# i2c_io_expander.net
KiCad netlist of a schematic drawn in EAGLE
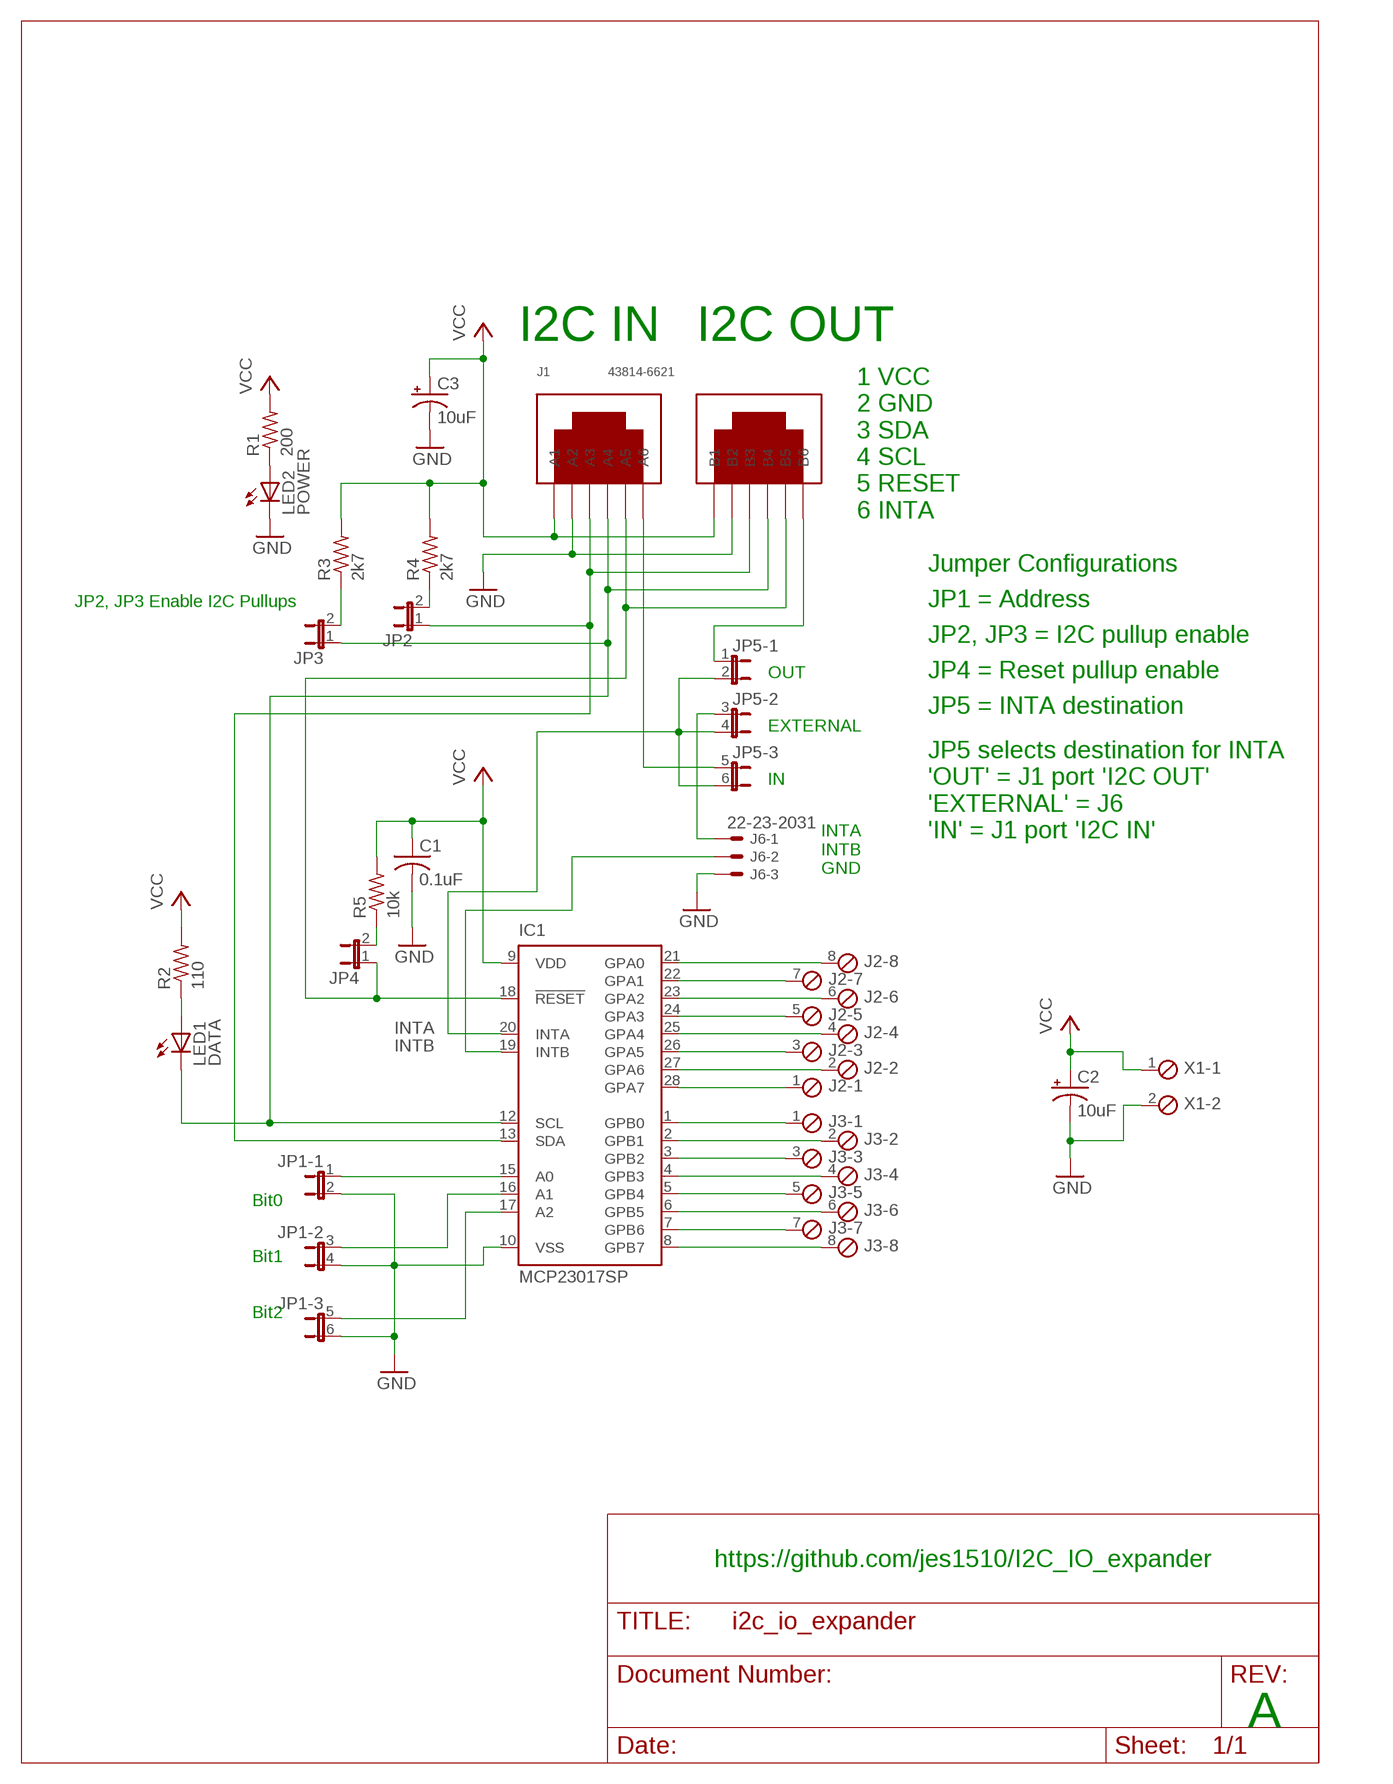
[diagram p0: schematic, sheet 1]

(export (version "E")
  (design (tool "Eeschema 10.0.6"))
  (components
    (comp (ref "C1")
      (value "0.1uF")
      (footprint "eagle-import:C025-025X050")
      (libsource (lib "eagle-import") (part "C-US025-025X050"))
    )
    (comp (ref "C2")
      (value "10uF")
      (footprint "eagle-import:E5-6")
      (libsource (lib "eagle-import") (part "CPOL-USE5-6"))
    )
    (comp (ref "C3")
      (value "10uF")
      (footprint "eagle-import:E5-6")
      (libsource (lib "eagle-import") (part "CPOL-USE5-6"))
    )
    (comp (ref "IC1")
      (value "MCP23017SP")
      (footprint "eagle-import:DIL28-3")
      (libsource (lib "eagle-import") (part "MCP23017SP"))
    )
    (comp (ref "J1")
      (value "43814-6621")
      (footprint "eagle-import:43814-6621")
      (fields (field (name "MF") "MOLEX"))
      (libsource (lib "eagle-import") (part "43814-6621"))
    )
    (comp (ref "J2")
      (value "MPT8")
      (footprint "eagle-import:8POL254")
      (fields
        (field (name "MF") "FARNELL")
        (field (name "MPN") "1725711")
        (field (name "OC_NEWARK") "71C4111")
      )
      (libsource (lib "eagle-import") (part "MPT8"))
    )
    (comp (ref "J3")
      (value "MPT8")
      (footprint "eagle-import:8POL254")
      (fields
        (field (name "MF") "FARNELL")
        (field (name "MPN") "1725711")
        (field (name "OC_FARNELL") "1725711")
        (field (name "OC_NEWARK") "71C4111")
      )
      (libsource (lib "eagle-import") (part "MPT8"))
    )
    (comp (ref "J6")
      (value "22-23-2031")
      (footprint "eagle-import:22-23-2031")
      (fields (field (name "MF") "MOLEX") (field (name "OC_NEWARK") "unknown"))
      (libsource (lib "eagle-import") (part "22-23-2031"))
    )
    (comp (ref "JP1")
      (value "JP3QE")
      (footprint "eagle-import:JP3Q")
      (fields (field (name "OC_NEWARK") "unknown"))
      (libsource (lib "eagle-import") (part "JP3QE"))
    )
    (comp (ref "JP2")
      (value "JP1E")
      (footprint "eagle-import:JP1")
      (libsource (lib "eagle-import") (part "JP1E"))
    )
    (comp (ref "JP3")
      (value "JP1E")
      (footprint "eagle-import:JP1")
      (libsource (lib "eagle-import") (part "JP1E"))
    )
    (comp (ref "JP4")
      (value "JP1E")
      (footprint "eagle-import:JP1")
      (libsource (lib "eagle-import") (part "JP1E"))
    )
    (comp (ref "JP5")
      (value "JP3QE")
      (footprint "eagle-import:JP3Q")
      (fields (field (name "OC_NEWARK") "unknown"))
      (libsource (lib "eagle-import") (part "JP3QE"))
    )
    (comp (ref "LED1")
      (value "DATA")
      (footprint "eagle-import:SMARTLED-TTW")
      (libsource (lib "eagle-import") (part "LED"))
    )
    (comp (ref "LED2")
      (value "POWER")
      (footprint "eagle-import:SMARTLED-TTW")
      (libsource (lib "eagle-import") (part "LED"))
    )
    (comp (ref "R1")
      (value "200")
      (footprint "eagle-import:R0603")
      (libsource (lib "eagle-import") (part "R-US_R0603"))
    )
    (comp (ref "R2")
      (value "110")
      (footprint "eagle-import:R0603")
      (libsource (lib "eagle-import") (part "R-US_R0603"))
    )
    (comp (ref "R3")
      (value "2k7")
      (footprint "eagle-import:R0603")
      (libsource (lib "eagle-import") (part "R-US_R0603"))
    )
    (comp (ref "R4")
      (value "2k7")
      (footprint "eagle-import:R0603")
      (libsource (lib "eagle-import") (part "R-US_R0603"))
    )
    (comp (ref "R5")
      (value "10k")
      (footprint "eagle-import:R0603")
      (libsource (lib "eagle-import") (part "R-US_R0603"))
    )
    (comp (ref "X1")
      (value "MPT2")
      (footprint "eagle-import:2POL254")
      (libsource (lib "eagle-import") (part "MPT2"))
    )
  )
  (nets
    (net (code "1") (name "/INTA") (class "Default")
      (node (ref "IC1") (pin "20") (pinfunction "INTA_20") (pintype "output"))
      (node (ref "JP5") (pin "2") (pinfunction "2_2") (pintype "passive"))
      (node (ref "JP5") (pin "4") (pinfunction "2_4") (pintype "passive"))
      (node (ref "JP5") (pin "6") (pinfunction "2_6") (pintype "passive"))
    )
    (net (code "2") (name "/INTB") (class "Default")
      (node (ref "IC1") (pin "19") (pinfunction "INTB_19") (pintype "output"))
      (node (ref "J6") (pin "2") (pinfunction "S_2") (pintype "passive"))
    )
    (net (code "3") (name "GND") (class "Default")
      (node (ref "C1") (pin "2") (pinfunction "2_2") (pintype "passive"))
      (node (ref "C2") (pin "-") (pinfunction "-_-") (pintype "passive"))
      (node (ref "C3") (pin "-") (pinfunction "-_-") (pintype "passive"))
      (node (ref "IC1") (pin "10") (pinfunction "VSS_10") (pintype "power_in"))
      (node (ref "J1") (pin "A2") (pinfunction "A2_A2") (pintype "bidirectional"))
      (node (ref "J1") (pin "B2") (pinfunction "B2_B2") (pintype "bidirectional"))
      (node (ref "J6") (pin "3") (pinfunction "S_3") (pintype "passive"))
      (node (ref "JP1") (pin "2") (pinfunction "2_2") (pintype "passive"))
      (node (ref "JP1") (pin "4") (pinfunction "2_4") (pintype "passive"))
      (node (ref "JP1") (pin "6") (pinfunction "2_6") (pintype "passive"))
      (node (ref "LED2") (pin "C@1") (pinfunction "C_C@1") (pintype "passive"))
      (node (ref "X1") (pin "2") (pinfunction "1_2") (pintype "passive"))
    )
    (net (code "4") (name "Net-(IC1-A0)") (class "Default")
      (node (ref "IC1") (pin "15") (pinfunction "A0_15") (pintype "input"))
      (node (ref "JP1") (pin "1") (pinfunction "1_1") (pintype "passive"))
    )
    (net (code "5") (name "Net-(IC1-A1)") (class "Default")
      (node (ref "IC1") (pin "16") (pinfunction "A1_16") (pintype "input"))
      (node (ref "JP1") (pin "3") (pinfunction "1_3") (pintype "passive"))
    )
    (net (code "6") (name "Net-(IC1-A2)") (class "Default")
      (node (ref "IC1") (pin "17") (pinfunction "A2_17") (pintype "input"))
      (node (ref "JP1") (pin "5") (pinfunction "1_5") (pintype "passive"))
    )
    (net (code "7") (name "Net-(IC1-GPA0)") (class "Default")
      (node (ref "IC1") (pin "21") (pinfunction "GPA0_21") (pintype "bidirectional"))
      (node (ref "J2") (pin "8") (pinfunction "1_8") (pintype "passive"))
    )
    (net (code "8") (name "Net-(IC1-GPA1)") (class "Default")
      (node (ref "IC1") (pin "22") (pinfunction "GPA1_22") (pintype "bidirectional"))
      (node (ref "J2") (pin "7") (pinfunction "1_7") (pintype "passive"))
    )
    (net (code "9") (name "Net-(IC1-GPA2)") (class "Default")
      (node (ref "IC1") (pin "23") (pinfunction "GPA2_23") (pintype "bidirectional"))
      (node (ref "J2") (pin "6") (pinfunction "1_6") (pintype "passive"))
    )
    (net (code "10") (name "Net-(IC1-GPA3)") (class "Default")
      (node (ref "IC1") (pin "24") (pinfunction "GPA3_24") (pintype "bidirectional"))
      (node (ref "J2") (pin "5") (pinfunction "1_5") (pintype "passive"))
    )
    (net (code "11") (name "Net-(IC1-GPA4)") (class "Default")
      (node (ref "IC1") (pin "25") (pinfunction "GPA4_25") (pintype "bidirectional"))
      (node (ref "J2") (pin "4") (pinfunction "1_4") (pintype "passive"))
    )
    (net (code "12") (name "Net-(IC1-GPA5)") (class "Default")
      (node (ref "IC1") (pin "26") (pinfunction "GPA5_26") (pintype "bidirectional"))
      (node (ref "J2") (pin "3") (pinfunction "1_3") (pintype "passive"))
    )
    (net (code "13") (name "Net-(IC1-GPA6)") (class "Default")
      (node (ref "IC1") (pin "27") (pinfunction "GPA6_27") (pintype "bidirectional"))
      (node (ref "J2") (pin "2") (pinfunction "1_2") (pintype "passive"))
    )
    (net (code "14") (name "Net-(IC1-GPA7)") (class "Default")
      (node (ref "IC1") (pin "28") (pinfunction "GPA7_28") (pintype "bidirectional"))
      (node (ref "J2") (pin "1") (pinfunction "1_1") (pintype "passive"))
    )
    (net (code "15") (name "Net-(IC1-GPB0)") (class "Default")
      (node (ref "IC1") (pin "1") (pinfunction "GPB0_1") (pintype "bidirectional"))
      (node (ref "J3") (pin "1") (pinfunction "1_1") (pintype "passive"))
    )
    (net (code "16") (name "Net-(IC1-GPB1)") (class "Default")
      (node (ref "IC1") (pin "2") (pinfunction "GPB1_2") (pintype "bidirectional"))
      (node (ref "J3") (pin "2") (pinfunction "1_2") (pintype "passive"))
    )
    (net (code "17") (name "Net-(IC1-GPB2)") (class "Default")
      (node (ref "IC1") (pin "3") (pinfunction "GPB2_3") (pintype "bidirectional"))
      (node (ref "J3") (pin "3") (pinfunction "1_3") (pintype "passive"))
    )
    (net (code "18") (name "Net-(IC1-GPB3)") (class "Default")
      (node (ref "IC1") (pin "4") (pinfunction "GPB3_4") (pintype "bidirectional"))
      (node (ref "J3") (pin "4") (pinfunction "1_4") (pintype "passive"))
    )
    (net (code "19") (name "Net-(IC1-GPB4)") (class "Default")
      (node (ref "IC1") (pin "5") (pinfunction "GPB4_5") (pintype "bidirectional"))
      (node (ref "J3") (pin "5") (pinfunction "1_5") (pintype "passive"))
    )
    (net (code "20") (name "Net-(IC1-GPB5)") (class "Default")
      (node (ref "IC1") (pin "6") (pinfunction "GPB5_6") (pintype "bidirectional"))
      (node (ref "J3") (pin "6") (pinfunction "1_6") (pintype "passive"))
    )
    (net (code "21") (name "Net-(IC1-GPB6)") (class "Default")
      (node (ref "IC1") (pin "7") (pinfunction "GPB6_7") (pintype "bidirectional"))
      (node (ref "J3") (pin "7") (pinfunction "1_7") (pintype "passive"))
    )
    (net (code "22") (name "Net-(IC1-GPB7)") (class "Default")
      (node (ref "IC1") (pin "8") (pinfunction "GPB7_8") (pintype "bidirectional"))
      (node (ref "J3") (pin "8") (pinfunction "1_8") (pintype "passive"))
    )
    (net (code "23") (name "Net-(IC1-SCL)") (class "Default")
      (node (ref "IC1") (pin "12") (pinfunction "SCL_12") (pintype "input"))
      (node (ref "J1") (pin "A4") (pinfunction "A4_A4") (pintype "bidirectional"))
      (node (ref "J1") (pin "B4") (pinfunction "B4_B4") (pintype "bidirectional"))
      (node (ref "JP3") (pin "1") (pinfunction "1_1") (pintype "passive"))
      (node (ref "LED1") (pin "C@1") (pinfunction "C_C@1") (pintype "passive"))
    )
    (net (code "24") (name "Net-(IC1-SDA)") (class "Default")
      (node (ref "IC1") (pin "13") (pinfunction "SDA_13") (pintype "bidirectional"))
      (node (ref "J1") (pin "A3") (pinfunction "A3_A3") (pintype "bidirectional"))
      (node (ref "J1") (pin "B3") (pinfunction "B3_B3") (pintype "bidirectional"))
      (node (ref "JP2") (pin "1") (pinfunction "1_1") (pintype "passive"))
    )
    (net (code "25") (name "Net-(IC1-~{RESET})") (class "Default")
      (node (ref "IC1") (pin "18") (pinfunction "~{RESET}_18") (pintype "input"))
      (node (ref "J1") (pin "A5") (pinfunction "A5_A5") (pintype "bidirectional"))
      (node (ref "J1") (pin "B5") (pinfunction "B5_B5") (pintype "bidirectional"))
      (node (ref "JP4") (pin "1") (pinfunction "1_1") (pintype "passive"))
    )
    (net (code "26") (name "Net-(J1-PadB6)") (class "Default")
      (node (ref "J1") (pin "B6") (pinfunction "B6_B6") (pintype "bidirectional"))
      (node (ref "JP5") (pin "1") (pinfunction "1_1") (pintype "passive"))
    )
    (net (code "27") (name "Net-(J6A-S)") (class "Default")
      (node (ref "J6") (pin "1") (pinfunction "S_1") (pintype "passive"))
      (node (ref "JP5") (pin "3") (pinfunction "1_3") (pintype "passive"))
    )
    (net (code "28") (name "Net-(JP2-Pad2)") (class "Default")
      (node (ref "JP2") (pin "2") (pinfunction "2_2") (pintype "passive"))
      (node (ref "R4") (pin "1") (pinfunction "1_1") (pintype "passive"))
    )
    (net (code "29") (name "Net-(JP3-Pad2)") (class "Default")
      (node (ref "JP3") (pin "2") (pinfunction "2_2") (pintype "passive"))
      (node (ref "R3") (pin "1") (pinfunction "1_1") (pintype "passive"))
    )
    (net (code "30") (name "Net-(JP4-Pad2)") (class "Default")
      (node (ref "JP4") (pin "2") (pinfunction "2_2") (pintype "passive"))
      (node (ref "R5") (pin "1") (pinfunction "1_1") (pintype "passive"))
    )
    (net (code "31") (name "Net-(JP5C-1)") (class "Default")
      (node (ref "J1") (pin "A6") (pinfunction "A6_A6") (pintype "bidirectional"))
      (node (ref "JP5") (pin "5") (pinfunction "1_5") (pintype "passive"))
    )
    (net (code "32") (name "Net-(LED1-A)") (class "Default")
      (node (ref "LED1") (pin "A@1") (pinfunction "A_A@1") (pintype "passive"))
      (node (ref "R2") (pin "1") (pinfunction "1_1") (pintype "passive"))
    )
    (net (code "33") (name "Net-(LED2-A)") (class "Default")
      (node (ref "LED2") (pin "A@1") (pinfunction "A_A@1") (pintype "passive"))
      (node (ref "R1") (pin "1") (pinfunction "1_1") (pintype "passive"))
    )
    (net (code "34") (name "VCC") (class "Default")
      (node (ref "C1") (pin "1") (pinfunction "1_1") (pintype "passive"))
      (node (ref "C2") (pin "+") (pinfunction "+_+") (pintype "passive"))
      (node (ref "C3") (pin "+") (pinfunction "+_+") (pintype "passive"))
      (node (ref "IC1") (pin "9") (pinfunction "VDD_9") (pintype "power_in"))
      (node (ref "J1") (pin "A1") (pinfunction "A1_A1") (pintype "bidirectional"))
      (node (ref "J1") (pin "B1") (pinfunction "B1_B1") (pintype "bidirectional"))
      (node (ref "R1") (pin "2") (pinfunction "2_2") (pintype "passive"))
      (node (ref "R2") (pin "2") (pinfunction "2_2") (pintype "passive"))
      (node (ref "R3") (pin "2") (pinfunction "2_2") (pintype "passive"))
      (node (ref "R4") (pin "2") (pinfunction "2_2") (pintype "passive"))
      (node (ref "R5") (pin "2") (pinfunction "2_2") (pintype "passive"))
      (node (ref "X1") (pin "1") (pinfunction "1_1") (pintype "passive"))
    )
  )
)
